# smog_v1_1_ctrl.net
KiCad netlist of a schematic drawn in EAGLE
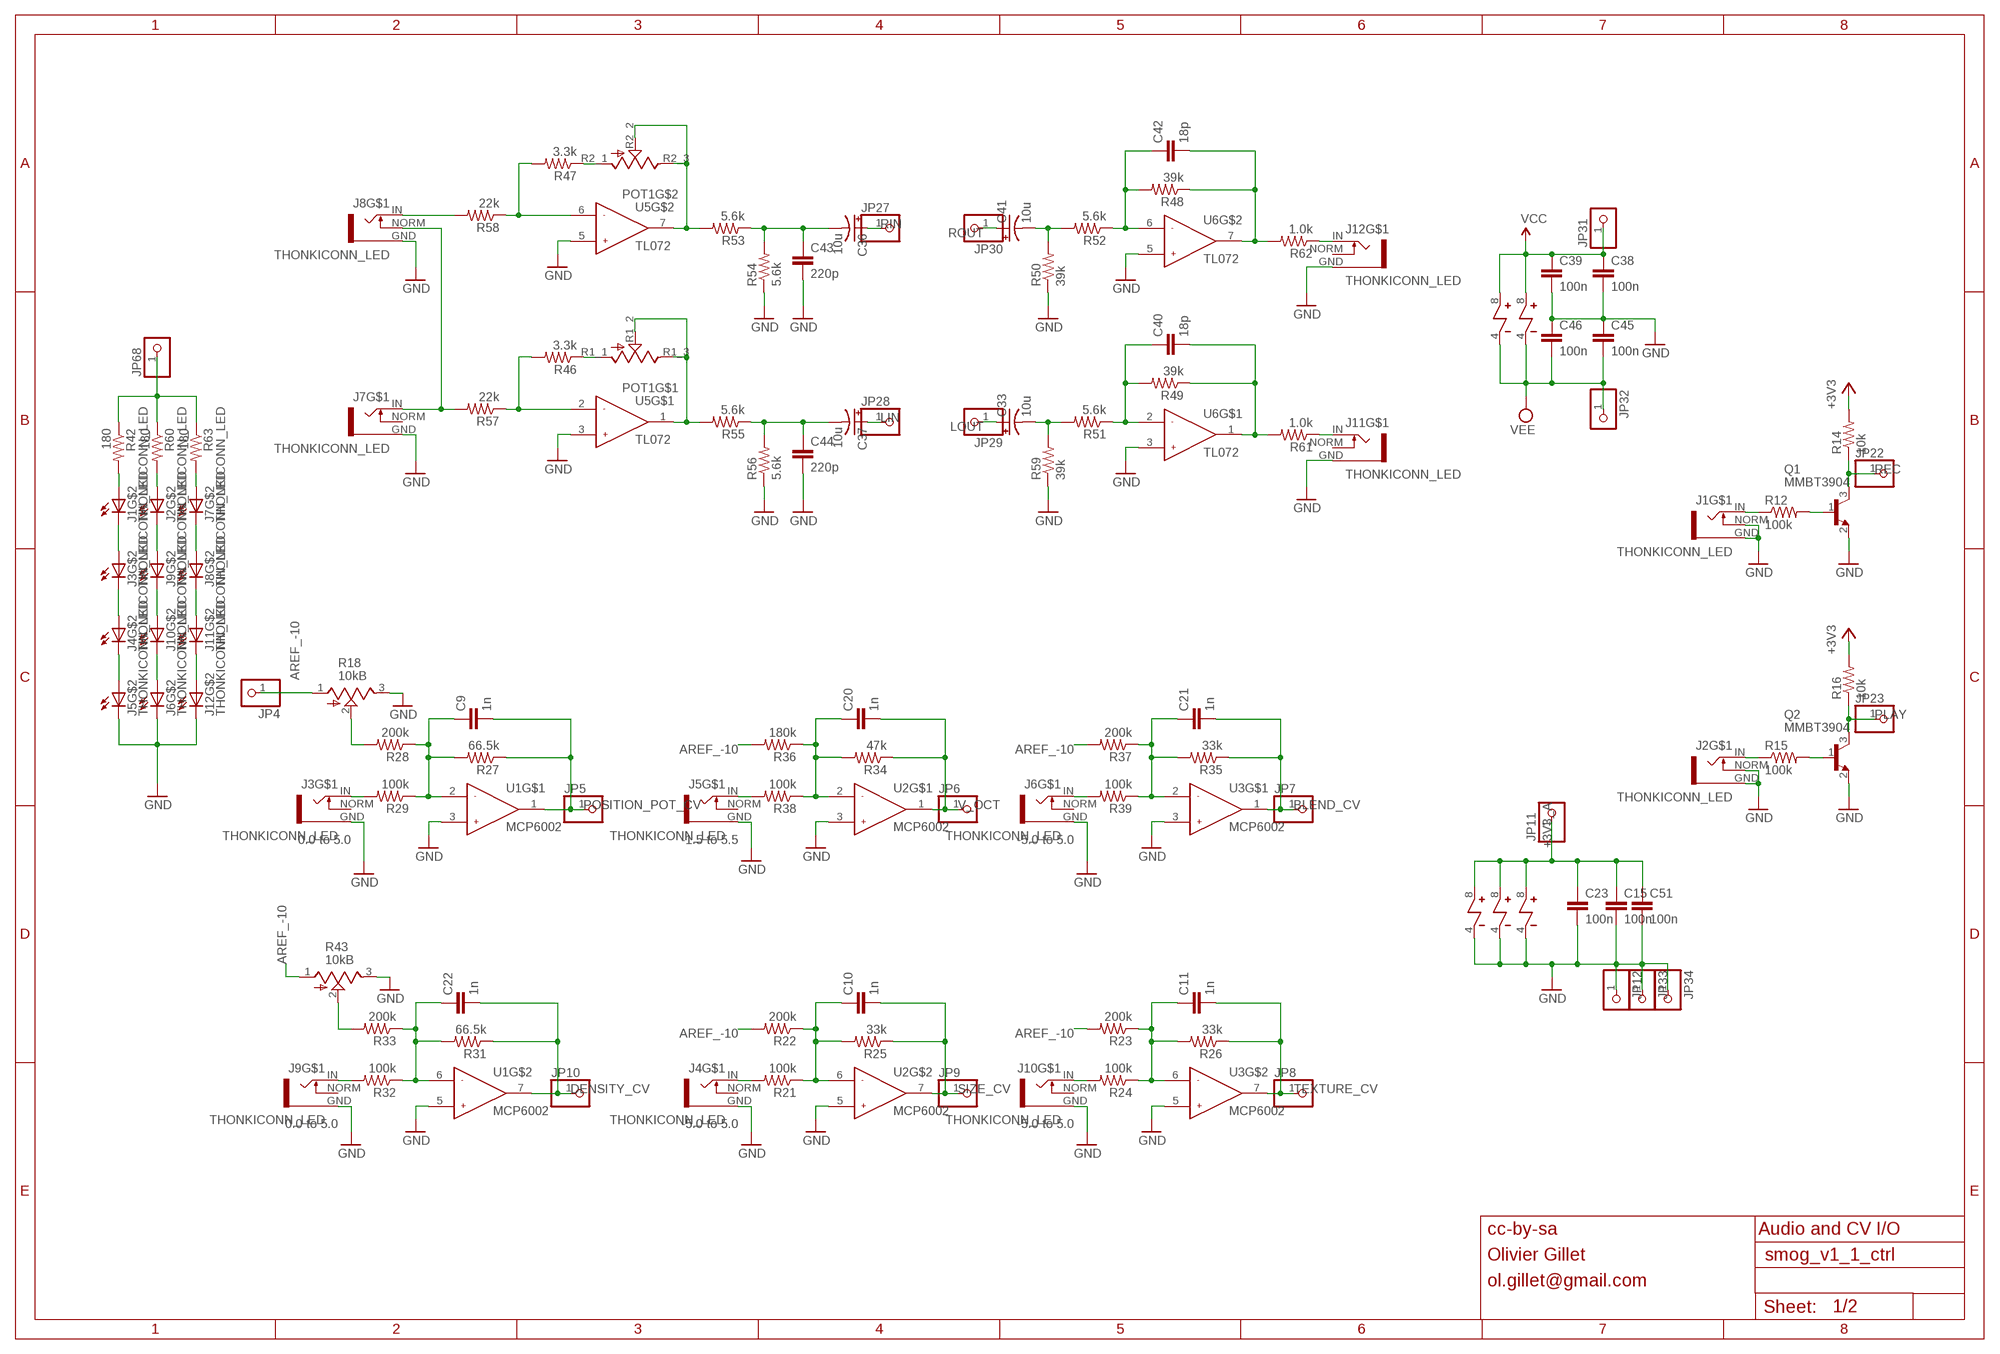
[diagram p0: schematic, sheet 1]
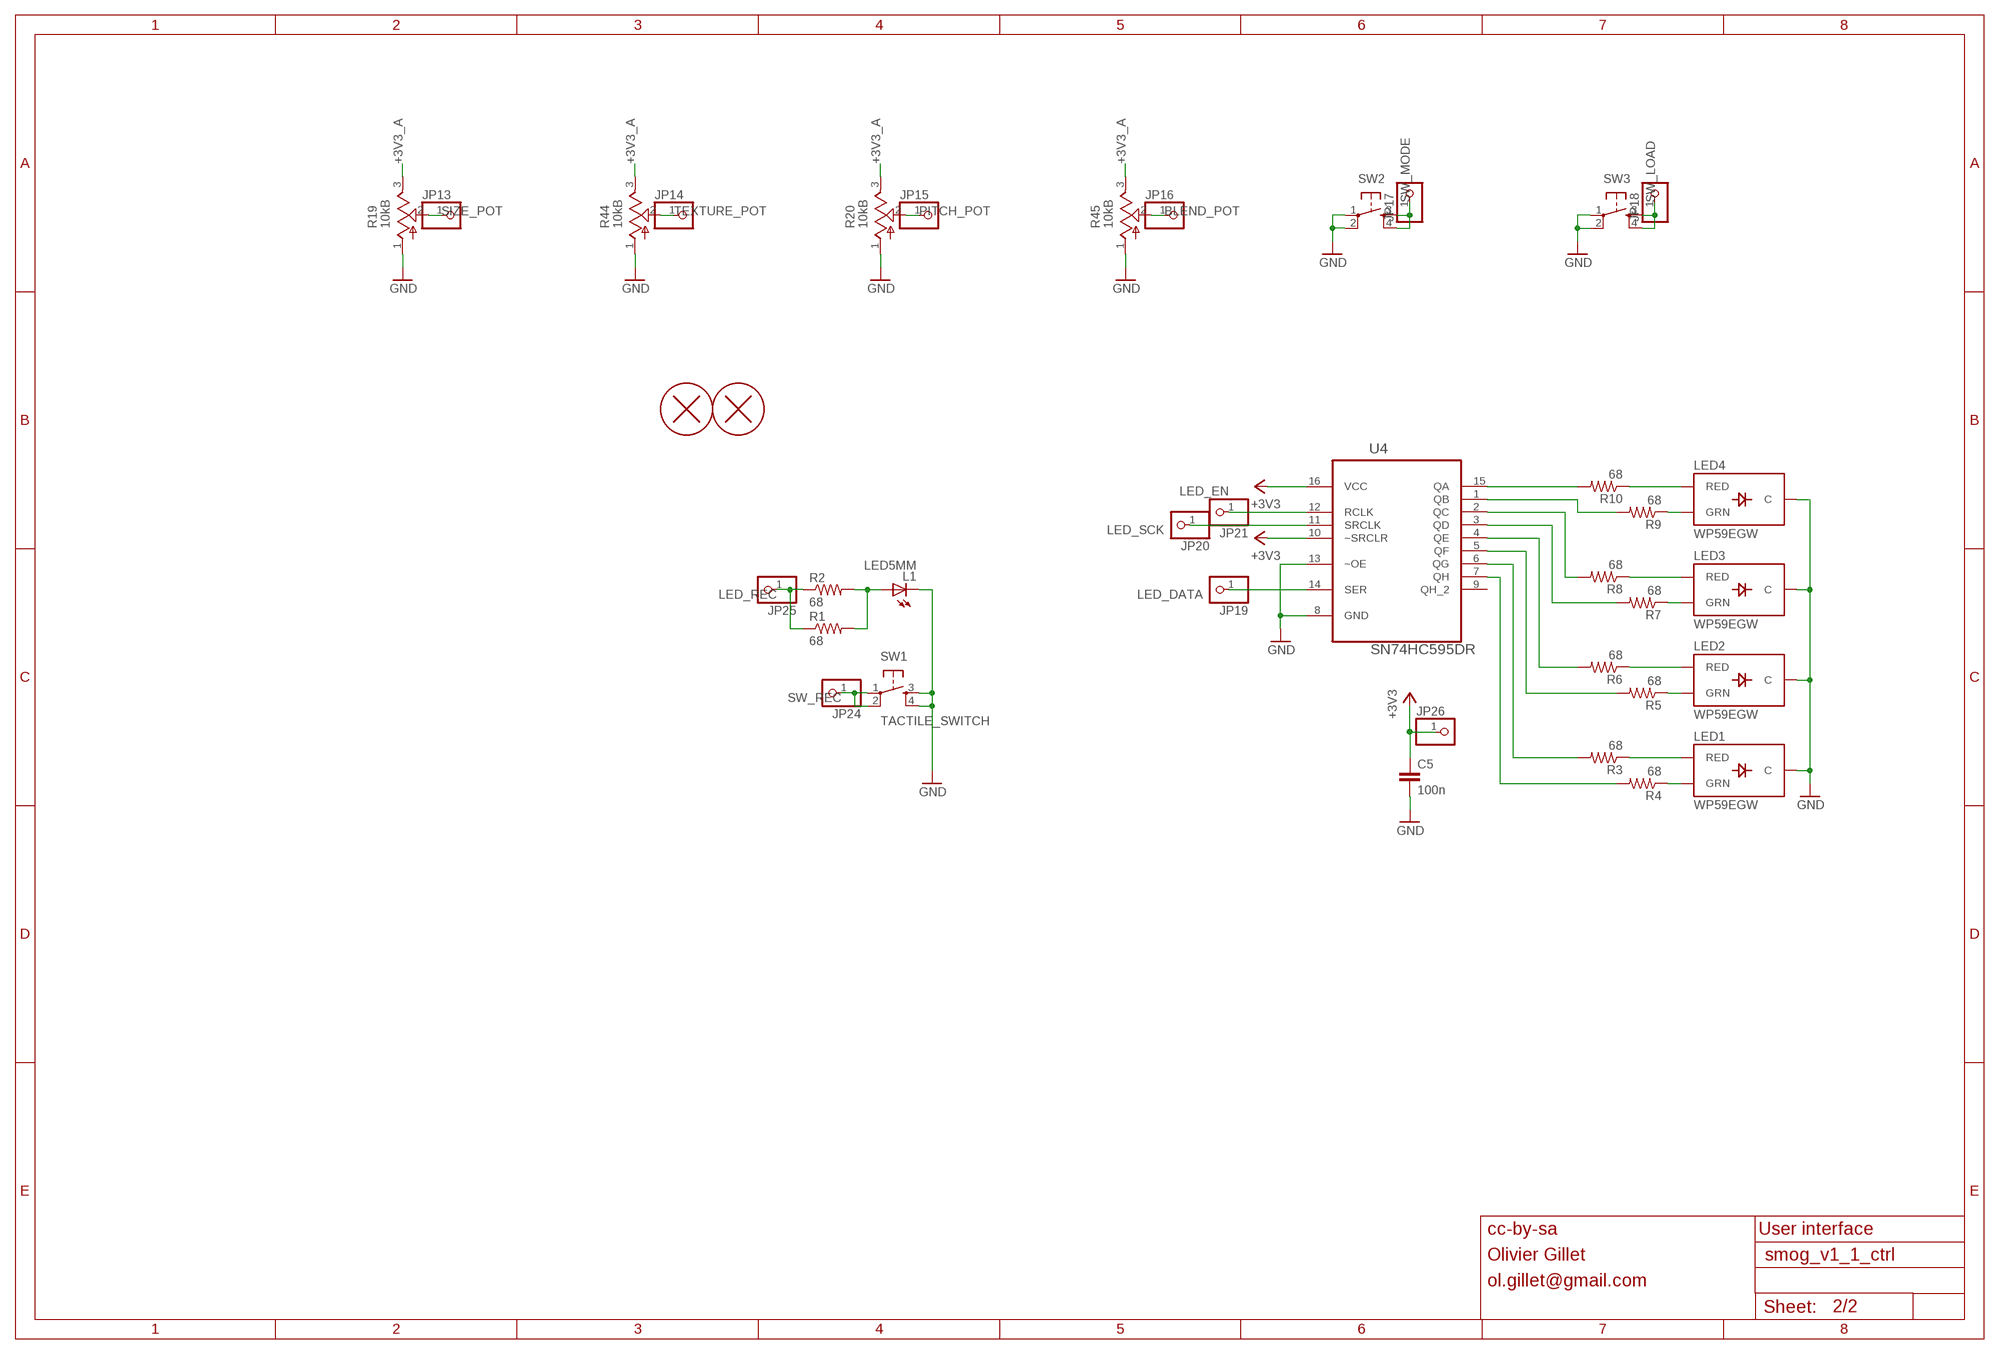
[diagram p1: schematic, sheet 2]

(export (version "E")
  (design (tool "Eeschema 10.0.6"))
  (components
    (comp (ref "C9")
      (value "1n")
      (footprint "eagle-import:RESISTOR_0603")
      (libsource (lib "eagle-import") (part "CAPACITOR"))
    )
    (comp (ref "C10")
      (value "1n")
      (footprint "eagle-import:RESISTOR_0603")
      (libsource (lib "eagle-import") (part "CAPACITOR"))
    )
    (comp (ref "C11")
      (value "1n")
      (footprint "eagle-import:RESISTOR_0603")
      (libsource (lib "eagle-import") (part "CAPACITOR"))
    )
    (comp (ref "C15")
      (value "100n")
      (footprint "eagle-import:RESISTOR_0603")
      (libsource (lib "eagle-import") (part "CAPACITOR"))
    )
    (comp (ref "C20")
      (value "1n")
      (footprint "eagle-import:RESISTOR_0603")
      (libsource (lib "eagle-import") (part "CAPACITOR"))
    )
    (comp (ref "C21")
      (value "1n")
      (footprint "eagle-import:RESISTOR_0603")
      (libsource (lib "eagle-import") (part "CAPACITOR"))
    )
    (comp (ref "C22")
      (value "1n")
      (footprint "eagle-import:RESISTOR_0603")
      (libsource (lib "eagle-import") (part "CAPACITOR"))
    )
    (comp (ref "C23")
      (value "100n")
      (footprint "eagle-import:RESISTOR_0603")
      (libsource (lib "eagle-import") (part "CAPACITOR"))
    )
    (comp (ref "C33")
      (value "10u")
      (footprint "eagle-import:PANASONIC_B")
      (libsource (lib "eagle-import") (part "CAP_POL"))
    )
    (comp (ref "C36")
      (value "10u")
      (footprint "eagle-import:PANASONIC_B")
      (libsource (lib "eagle-import") (part "CAP_POL"))
    )
    (comp (ref "C37")
      (value "10u")
      (footprint "eagle-import:PANASONIC_B")
      (libsource (lib "eagle-import") (part "CAP_POL"))
    )
    (comp (ref "C38")
      (value "100n")
      (footprint "eagle-import:RESISTOR_0603")
      (libsource (lib "eagle-import") (part "CAPACITOR"))
    )
    (comp (ref "C39")
      (value "100n")
      (footprint "eagle-import:RESISTOR_0603")
      (libsource (lib "eagle-import") (part "CAPACITOR"))
    )
    (comp (ref "C40")
      (value "18p")
      (footprint "eagle-import:RESISTOR_0603")
      (libsource (lib "eagle-import") (part "CAPACITOR"))
    )
    (comp (ref "C41")
      (value "10u")
      (footprint "eagle-import:PANASONIC_B")
      (libsource (lib "eagle-import") (part "CAP_POL"))
    )
    (comp (ref "C42")
      (value "18p")
      (footprint "eagle-import:RESISTOR_0603")
      (libsource (lib "eagle-import") (part "CAPACITOR"))
    )
    (comp (ref "C43")
      (value "220p")
      (footprint "eagle-import:RESISTOR_0603")
      (libsource (lib "eagle-import") (part "CAPACITOR"))
    )
    (comp (ref "C44")
      (value "220p")
      (footprint "eagle-import:RESISTOR_0603")
      (libsource (lib "eagle-import") (part "CAPACITOR"))
    )
    (comp (ref "C45")
      (value "100n")
      (footprint "eagle-import:RESISTOR_0603")
      (libsource (lib "eagle-import") (part "CAPACITOR"))
    )
    (comp (ref "C46")
      (value "100n")
      (footprint "eagle-import:RESISTOR_0603")
      (libsource (lib "eagle-import") (part "CAPACITOR"))
    )
    (comp (ref "C51")
      (value "100n")
      (footprint "eagle-import:RESISTOR_0603")
      (libsource (lib "eagle-import") (part "CAPACITOR"))
    )
    (comp (ref "J1")
      (value "THONKICONN_LED")
      (footprint "eagle-import:LED_JACK")
      (libsource (lib "eagle-import") (part "THONKICONN_LED"))
    )
    (comp (ref "J2")
      (value "THONKICONN_LED")
      (footprint "eagle-import:LED_JACK")
      (libsource (lib "eagle-import") (part "THONKICONN_LED"))
    )
    (comp (ref "J3")
      (value "THONKICONN_LED")
      (footprint "eagle-import:LED_JACK")
      (libsource (lib "eagle-import") (part "THONKICONN_LED"))
    )
    (comp (ref "J4")
      (value "THONKICONN_LED")
      (footprint "eagle-import:LED_JACK")
      (libsource (lib "eagle-import") (part "THONKICONN_LED"))
    )
    (comp (ref "J5")
      (value "THONKICONN_LED")
      (footprint "eagle-import:LED_JACK")
      (libsource (lib "eagle-import") (part "THONKICONN_LED"))
    )
    (comp (ref "J6")
      (value "THONKICONN_LED")
      (footprint "eagle-import:LED_JACK")
      (libsource (lib "eagle-import") (part "THONKICONN_LED"))
    )
    (comp (ref "J7")
      (value "THONKICONN_LED")
      (footprint "eagle-import:LED_JACK")
      (libsource (lib "eagle-import") (part "THONKICONN_LED"))
    )
    (comp (ref "J8")
      (value "THONKICONN_LED")
      (footprint "eagle-import:LED_JACK")
      (libsource (lib "eagle-import") (part "THONKICONN_LED"))
    )
    (comp (ref "J9")
      (value "THONKICONN_LED")
      (footprint "eagle-import:LED_JACK")
      (libsource (lib "eagle-import") (part "THONKICONN_LED"))
    )
    (comp (ref "J10")
      (value "THONKICONN_LED")
      (footprint "eagle-import:LED_JACK")
      (libsource (lib "eagle-import") (part "THONKICONN_LED"))
    )
    (comp (ref "J11")
      (value "THONKICONN_LED")
      (footprint "eagle-import:LED_JACK")
      (libsource (lib "eagle-import") (part "THONKICONN_LED"))
    )
    (comp (ref "J12")
      (value "THONKICONN_LED")
      (footprint "eagle-import:LED_JACK")
      (libsource (lib "eagle-import") (part "THONKICONN_LED"))
    )
    (comp (ref "JP4")
      (value "PINHD-1X1")
      (footprint "eagle-import:1X01")
      (libsource (lib "eagle-import") (part "PINHD-1X1"))
    )
    (comp (ref "JP5")
      (value "PINHD-1X1")
      (footprint "eagle-import:1X01")
      (libsource (lib "eagle-import") (part "PINHD-1X1"))
    )
    (comp (ref "JP6")
      (value "PINHD-1X1")
      (footprint "eagle-import:1X01")
      (libsource (lib "eagle-import") (part "PINHD-1X1"))
    )
    (comp (ref "JP7")
      (value "PINHD-1X1")
      (footprint "eagle-import:1X01")
      (libsource (lib "eagle-import") (part "PINHD-1X1"))
    )
    (comp (ref "JP8")
      (value "PINHD-1X1")
      (footprint "eagle-import:1X01")
      (libsource (lib "eagle-import") (part "PINHD-1X1"))
    )
    (comp (ref "JP9")
      (value "PINHD-1X1")
      (footprint "eagle-import:1X01")
      (libsource (lib "eagle-import") (part "PINHD-1X1"))
    )
    (comp (ref "JP10")
      (value "PINHD-1X1")
      (footprint "eagle-import:1X01")
      (libsource (lib "eagle-import") (part "PINHD-1X1"))
    )
    (comp (ref "JP11")
      (value "PINHD-1X1")
      (footprint "eagle-import:1X01")
      (libsource (lib "eagle-import") (part "PINHD-1X1"))
    )
    (comp (ref "JP12")
      (value "PINHD-1X1")
      (footprint "eagle-import:1X01")
      (libsource (lib "eagle-import") (part "PINHD-1X1"))
    )
    (comp (ref "JP22")
      (value "PINHD-1X1")
      (footprint "eagle-import:1X01")
      (libsource (lib "eagle-import") (part "PINHD-1X1"))
    )
    (comp (ref "JP23")
      (value "PINHD-1X1")
      (footprint "eagle-import:1X01")
      (libsource (lib "eagle-import") (part "PINHD-1X1"))
    )
    (comp (ref "JP27")
      (value "PINHD-1X1")
      (footprint "eagle-import:1X01")
      (libsource (lib "eagle-import") (part "PINHD-1X1"))
    )
    (comp (ref "JP28")
      (value "PINHD-1X1")
      (footprint "eagle-import:1X01")
      (libsource (lib "eagle-import") (part "PINHD-1X1"))
    )
    (comp (ref "JP29")
      (value "PINHD-1X1")
      (footprint "eagle-import:1X01")
      (libsource (lib "eagle-import") (part "PINHD-1X1"))
    )
    (comp (ref "JP30")
      (value "PINHD-1X1")
      (footprint "eagle-import:1X01")
      (libsource (lib "eagle-import") (part "PINHD-1X1"))
    )
    (comp (ref "JP31")
      (value "PINHD-1X1")
      (footprint "eagle-import:1X01")
      (libsource (lib "eagle-import") (part "PINHD-1X1"))
    )
    (comp (ref "JP32")
      (value "PINHD-1X1")
      (footprint "eagle-import:1X01")
      (libsource (lib "eagle-import") (part "PINHD-1X1"))
    )
    (comp (ref "JP33")
      (value "PINHD-1X1")
      (footprint "eagle-import:1X01")
      (libsource (lib "eagle-import") (part "PINHD-1X1"))
    )
    (comp (ref "JP34")
      (value "PINHD-1X1")
      (footprint "eagle-import:1X01")
      (libsource (lib "eagle-import") (part "PINHD-1X1"))
    )
    (comp (ref "JP68")
      (value "PINHD-1X1")
      (footprint "eagle-import:1X01")
      (libsource (lib "eagle-import") (part "PINHD-1X1"))
    )
    (comp (ref "POT1")
      (value "POT_DUAL_THONK")
      (footprint "eagle-import:POT_DUAL_THONK")
      (libsource (lib "eagle-import") (part "POT_DUAL_THONK"))
    )
    (comp (ref "Q1")
      (value "MMBT3904")
      (footprint "eagle-import:SOT23")
      (libsource (lib "eagle-import") (part "MMBT3904SOT23"))
    )
    (comp (ref "Q2")
      (value "MMBT3904")
      (footprint "eagle-import:SOT23")
      (libsource (lib "eagle-import") (part "MMBT3904SOT23"))
    )
    (comp (ref "R12")
      (value "100k")
      (footprint "eagle-import:RESISTOR_0603")
      (libsource (lib "eagle-import") (part "RESISTOR"))
    )
    (comp (ref "R14")
      (value "10k")
      (footprint "eagle-import:RESISTOR_0603")
      (libsource (lib "eagle-import") (part "RESISTOR"))
    )
    (comp (ref "R15")
      (value "100k")
      (footprint "eagle-import:RESISTOR_0603")
      (libsource (lib "eagle-import") (part "RESISTOR"))
    )
    (comp (ref "R16")
      (value "10k")
      (footprint "eagle-import:RESISTOR_0603")
      (libsource (lib "eagle-import") (part "RESISTOR"))
    )
    (comp (ref "R18")
      (value "10kB")
      (footprint "eagle-import:ALPS_POT_VERTICAL")
      (libsource (lib "eagle-import") (part "POT_VERTICAL"))
    )
    (comp (ref "R21")
      (value "100k")
      (footprint "eagle-import:RESISTOR_0603")
      (libsource (lib "eagle-import") (part "RESISTOR"))
    )
    (comp (ref "R22")
      (value "200k")
      (footprint "eagle-import:RESISTOR_0603")
      (libsource (lib "eagle-import") (part "RESISTOR"))
    )
    (comp (ref "R23")
      (value "200k")
      (footprint "eagle-import:RESISTOR_0603")
      (libsource (lib "eagle-import") (part "RESISTOR"))
    )
    (comp (ref "R24")
      (value "100k")
      (footprint "eagle-import:RESISTOR_0603")
      (libsource (lib "eagle-import") (part "RESISTOR"))
    )
    (comp (ref "R25")
      (value "33k")
      (footprint "eagle-import:RESISTOR_0603")
      (libsource (lib "eagle-import") (part "RESISTOR"))
    )
    (comp (ref "R26")
      (value "33k")
      (footprint "eagle-import:RESISTOR_0603")
      (libsource (lib "eagle-import") (part "RESISTOR"))
    )
    (comp (ref "R27")
      (value "66.5k")
      (footprint "eagle-import:RESISTOR_0603")
      (libsource (lib "eagle-import") (part "RESISTOR"))
    )
    (comp (ref "R28")
      (value "200k")
      (footprint "eagle-import:RESISTOR_0603")
      (libsource (lib "eagle-import") (part "RESISTOR"))
    )
    (comp (ref "R29")
      (value "100k")
      (footprint "eagle-import:RESISTOR_0603")
      (libsource (lib "eagle-import") (part "RESISTOR"))
    )
    (comp (ref "R31")
      (value "66.5k")
      (footprint "eagle-import:RESISTOR_0603")
      (libsource (lib "eagle-import") (part "RESISTOR"))
    )
    (comp (ref "R32")
      (value "100k")
      (footprint "eagle-import:RESISTOR_0603")
      (libsource (lib "eagle-import") (part "RESISTOR"))
    )
    (comp (ref "R33")
      (value "200k")
      (footprint "eagle-import:RESISTOR_0603")
      (libsource (lib "eagle-import") (part "RESISTOR"))
    )
    (comp (ref "R34")
      (value "47k")
      (footprint "eagle-import:RESISTOR_0603")
      (libsource (lib "eagle-import") (part "RESISTOR"))
    )
    (comp (ref "R35")
      (value "33k")
      (footprint "eagle-import:RESISTOR_0603")
      (libsource (lib "eagle-import") (part "RESISTOR"))
    )
    (comp (ref "R36")
      (value "180k")
      (footprint "eagle-import:RESISTOR_0603")
      (libsource (lib "eagle-import") (part "RESISTOR"))
    )
    (comp (ref "R37")
      (value "200k")
      (footprint "eagle-import:RESISTOR_0603")
      (libsource (lib "eagle-import") (part "RESISTOR"))
    )
    (comp (ref "R38")
      (value "100k")
      (footprint "eagle-import:RESISTOR_0603")
      (libsource (lib "eagle-import") (part "RESISTOR"))
    )
    (comp (ref "R39")
      (value "100k")
      (footprint "eagle-import:RESISTOR_0603")
      (libsource (lib "eagle-import") (part "RESISTOR"))
    )
    (comp (ref "R42")
      (value "180")
      (footprint "eagle-import:RESISTOR_0603")
      (libsource (lib "eagle-import") (part "RESISTOR"))
    )
    (comp (ref "R43")
      (value "10kB")
      (footprint "eagle-import:ALPS_POT_VERTICAL")
      (libsource (lib "eagle-import") (part "POT_VERTICAL"))
    )
    (comp (ref "R46")
      (value "3.3k")
      (footprint "eagle-import:RESISTOR_0603")
      (libsource (lib "eagle-import") (part "RESISTOR"))
    )
    (comp (ref "R47")
      (value "3.3k")
      (footprint "eagle-import:RESISTOR_0603")
      (libsource (lib "eagle-import") (part "RESISTOR"))
    )
    (comp (ref "R48")
      (value "39k")
      (footprint "eagle-import:RESISTOR_0603")
      (libsource (lib "eagle-import") (part "RESISTOR"))
    )
    (comp (ref "R49")
      (value "39k")
      (footprint "eagle-import:RESISTOR_0603")
      (libsource (lib "eagle-import") (part "RESISTOR"))
    )
    (comp (ref "R50")
      (value "39k")
      (footprint "eagle-import:RESISTOR_0603")
      (libsource (lib "eagle-import") (part "RESISTOR"))
    )
    (comp (ref "R51")
      (value "5.6k")
      (footprint "eagle-import:RESISTOR_0603")
      (libsource (lib "eagle-import") (part "RESISTOR"))
    )
    (comp (ref "R52")
      (value "5.6k")
      (footprint "eagle-import:RESISTOR_0603")
      (libsource (lib "eagle-import") (part "RESISTOR"))
    )
    (comp (ref "R53")
      (value "5.6k")
      (footprint "eagle-import:RESISTOR_0603")
      (libsource (lib "eagle-import") (part "RESISTOR"))
    )
    (comp (ref "R54")
      (value "5.6k")
      (footprint "eagle-import:RESISTOR_0603")
      (libsource (lib "eagle-import") (part "RESISTOR"))
    )
    (comp (ref "R55")
      (value "5.6k")
      (footprint "eagle-import:RESISTOR_0603")
      (libsource (lib "eagle-import") (part "RESISTOR"))
    )
    (comp (ref "R56")
      (value "5.6k")
      (footprint "eagle-import:RESISTOR_0603")
      (libsource (lib "eagle-import") (part "RESISTOR"))
    )
    (comp (ref "R57")
      (value "22k")
      (footprint "eagle-import:RESISTOR_0603")
      (libsource (lib "eagle-import") (part "RESISTOR"))
    )
    (comp (ref "R58")
      (value "22k")
      (footprint "eagle-import:RESISTOR_0603")
      (libsource (lib "eagle-import") (part "RESISTOR"))
    )
    (comp (ref "R59")
      (value "39k")
      (footprint "eagle-import:RESISTOR_0603")
      (libsource (lib "eagle-import") (part "RESISTOR"))
    )
    (comp (ref "R60")
      (value "180")
      (footprint "eagle-import:RESISTOR_0603")
      (libsource (lib "eagle-import") (part "RESISTOR"))
    )
    (comp (ref "R61")
      (value "1.0k")
      (footprint "eagle-import:RESISTOR_0603")
      (libsource (lib "eagle-import") (part "RESISTOR"))
    )
    (comp (ref "R62")
      (value "1.0k")
      (footprint "eagle-import:RESISTOR_0603")
      (libsource (lib "eagle-import") (part "RESISTOR"))
    )
    (comp (ref "R63")
      (value "180")
      (footprint "eagle-import:RESISTOR_0603")
      (libsource (lib "eagle-import") (part "RESISTOR"))
    )
    (comp (ref "U1")
      (value "MCP6002")
      (footprint "eagle-import:SOIC8")
      (libsource (lib "eagle-import") (part "OPAMP_DUAL"))
    )
    (comp (ref "U2")
      (value "MCP6002")
      (footprint "eagle-import:SOIC8")
      (libsource (lib "eagle-import") (part "OPAMP_DUAL"))
    )
    (comp (ref "U3")
      (value "MCP6002")
      (footprint "eagle-import:SOIC8")
      (libsource (lib "eagle-import") (part "OPAMP_DUAL"))
    )
    (comp (ref "U5")
      (value "TL072")
      (footprint "eagle-import:SOIC8")
      (libsource (lib "eagle-import") (part "OPAMP_DUAL"))
    )
    (comp (ref "U6")
      (value "TL072")
      (footprint "eagle-import:SOIC8")
      (libsource (lib "eagle-import") (part "OPAMP_DUAL"))
    )
    (comp (ref "C5")
      (value "100n")
      (footprint "eagle-import:RESISTOR_0603")
      (libsource (lib "eagle-import") (part "CAPACITOR"))
    )
    (comp (ref "H1")
      (value "PCB_SCREW")
      (footprint "eagle-import:PCB_SCREW")
      (libsource (lib "eagle-import") (part "PCB_SCREW"))
    )
    (comp (ref "H2")
      (value "PCB_SCREW")
      (footprint "eagle-import:PCB_SCREW")
      (libsource (lib "eagle-import") (part "PCB_SCREW"))
    )
    (comp (ref "JP13")
      (value "PINHD-1X1")
      (footprint "eagle-import:1X01")
      (libsource (lib "eagle-import") (part "PINHD-1X1"))
    )
    (comp (ref "JP14")
      (value "PINHD-1X1")
      (footprint "eagle-import:1X01")
      (libsource (lib "eagle-import") (part "PINHD-1X1"))
    )
    (comp (ref "JP15")
      (value "PINHD-1X1")
      (footprint "eagle-import:1X01")
      (libsource (lib "eagle-import") (part "PINHD-1X1"))
    )
    (comp (ref "JP16")
      (value "PINHD-1X1")
      (footprint "eagle-import:1X01")
      (libsource (lib "eagle-import") (part "PINHD-1X1"))
    )
    (comp (ref "JP17")
      (value "PINHD-1X1")
      (footprint "eagle-import:1X01")
      (libsource (lib "eagle-import") (part "PINHD-1X1"))
    )
    (comp (ref "JP18")
      (value "PINHD-1X1")
      (footprint "eagle-import:1X01")
      (libsource (lib "eagle-import") (part "PINHD-1X1"))
    )
    (comp (ref "JP19")
      (value "PINHD-1X1")
      (footprint "eagle-import:1X01")
      (libsource (lib "eagle-import") (part "PINHD-1X1"))
    )
    (comp (ref "JP20")
      (value "PINHD-1X1")
      (footprint "eagle-import:1X01")
      (libsource (lib "eagle-import") (part "PINHD-1X1"))
    )
    (comp (ref "JP21")
      (value "PINHD-1X1")
      (footprint "eagle-import:1X01")
      (libsource (lib "eagle-import") (part "PINHD-1X1"))
    )
    (comp (ref "JP24")
      (value "PINHD-1X1")
      (footprint "eagle-import:1X01")
      (libsource (lib "eagle-import") (part "PINHD-1X1"))
    )
    (comp (ref "JP25")
      (value "PINHD-1X1")
      (footprint "eagle-import:1X01")
      (libsource (lib "eagle-import") (part "PINHD-1X1"))
    )
    (comp (ref "JP26")
      (value "PINHD-1X1")
      (footprint "eagle-import:1X01")
      (libsource (lib "eagle-import") (part "PINHD-1X1"))
    )
    (comp (ref "L1")
      (value "LED5MM")
      (footprint "eagle-import:LED_5MM")
      (libsource (lib "eagle-import") (part "LED5MM"))
    )
    (comp (ref "LED1")
      (value "WP59EGW")
      (footprint "eagle-import:LED_BICOLOR")
      (libsource (lib "eagle-import") (part "LED_BICOLOR_THROUGHHOLE"))
    )
    (comp (ref "LED2")
      (value "WP59EGW")
      (footprint "eagle-import:LED_BICOLOR")
      (libsource (lib "eagle-import") (part "LED_BICOLOR_THROUGHHOLE"))
    )
    (comp (ref "LED3")
      (value "WP59EGW")
      (footprint "eagle-import:LED_BICOLOR")
      (libsource (lib "eagle-import") (part "LED_BICOLOR_THROUGHHOLE"))
    )
    (comp (ref "LED4")
      (value "WP59EGW")
      (footprint "eagle-import:LED_BICOLOR")
      (libsource (lib "eagle-import") (part "LED_BICOLOR_THROUGHHOLE"))
    )
    (comp (ref "R1")
      (value "68")
      (footprint "eagle-import:RESISTOR_0603")
      (libsource (lib "eagle-import") (part "RESISTOR"))
    )
    (comp (ref "R2")
      (value "68")
      (footprint "eagle-import:RESISTOR_0603")
      (libsource (lib "eagle-import") (part "RESISTOR"))
    )
    (comp (ref "R3")
      (value "68")
      (footprint "eagle-import:RESISTOR_0603")
      (libsource (lib "eagle-import") (part "RESISTOR"))
    )
    (comp (ref "R4")
      (value "68")
      (footprint "eagle-import:RESISTOR_0603")
      (libsource (lib "eagle-import") (part "RESISTOR"))
    )
    (comp (ref "R5")
      (value "68")
      (footprint "eagle-import:RESISTOR_0603")
      (libsource (lib "eagle-import") (part "RESISTOR"))
    )
    (comp (ref "R6")
      (value "68")
      (footprint "eagle-import:RESISTOR_0603")
      (libsource (lib "eagle-import") (part "RESISTOR"))
    )
    (comp (ref "R7")
      (value "68")
      (footprint "eagle-import:RESISTOR_0603")
      (libsource (lib "eagle-import") (part "RESISTOR"))
    )
    (comp (ref "R8")
      (value "68")
      (footprint "eagle-import:RESISTOR_0603")
      (libsource (lib "eagle-import") (part "RESISTOR"))
    )
    (comp (ref "R9")
      (value "68")
      (footprint "eagle-import:RESISTOR_0603")
      (libsource (lib "eagle-import") (part "RESISTOR"))
    )
    (comp (ref "R10")
      (value "68")
      (footprint "eagle-import:RESISTOR_0603")
      (libsource (lib "eagle-import") (part "RESISTOR"))
    )
    (comp (ref "R19")
      (value "10kB")
      (footprint "eagle-import:ALPS_POT_VERTICAL")
      (libsource (lib "eagle-import") (part "POT_VERTICAL"))
    )
    (comp (ref "R20")
      (value "10kB")
      (footprint "eagle-import:ALPS_POT_VERTICAL")
      (libsource (lib "eagle-import") (part "POT_VERTICAL"))
    )
    (comp (ref "R44")
      (value "10kB")
      (footprint "eagle-import:ALPS_POT_VERTICAL")
      (libsource (lib "eagle-import") (part "POT_VERTICAL"))
    )
    (comp (ref "R45")
      (value "10kB")
      (footprint "eagle-import:ALPS_POT_VERTICAL")
      (libsource (lib "eagle-import") (part "POT_VERTICAL"))
    )
    (comp (ref "SW1")
      (value "TACTILE_SWITCH")
      (footprint "eagle-import:TACTILE-PTH")
      (libsource (lib "eagle-import") (part "TACTILE_SWITCH"))
    )
    (comp (ref "SW2")
      (value "TACTILE_SWITCH")
      (footprint "eagle-import:TACTILE-PTH")
      (libsource (lib "eagle-import") (part "TACTILE_SWITCH"))
    )
    (comp (ref "SW3")
      (value "TACTILE_SWITCH")
      (footprint "eagle-import:TACTILE-PTH")
      (libsource (lib "eagle-import") (part "TACTILE_SWITCH"))
    )
    (comp (ref "U4")
      (value "SN74HC595DR")
      (footprint "eagle-import:SOIC16")
      (libsource (lib "eagle-import") (part "SN74HC595DR"))
    )
  )
  (nets
    (net (code "1") (name "+3V3") (class "Default")
      (node (ref "C5") (pin "1") (pinfunction "1_1") (pintype "passive"))
      (node (ref "JP26") (pin "1") (pinfunction "1_1") (pintype "passive"))
      (node (ref "R14") (pin "2") (pinfunction "2_2") (pintype "passive"))
      (node (ref "R16") (pin "2") (pinfunction "2_2") (pintype "passive"))
      (node (ref "U4") (pin "10") (pinfunction "~{SRCLR}_10") (pintype "input"))
      (node (ref "U4") (pin "16") (pinfunction "VCC_16") (pintype "power_in"))
    )
    (net (code "2") (name "+3V3_A") (class "Default")
      (node (ref "C15") (pin "1") (pinfunction "1_1") (pintype "passive"))
      (node (ref "C23") (pin "1") (pinfunction "1_1") (pintype "passive"))
      (node (ref "C51") (pin "1") (pinfunction "1_1") (pintype "passive"))
      (node (ref "JP11") (pin "1") (pinfunction "1_1") (pintype "passive"))
      (node (ref "R19") (pin "3") (pinfunction "B_3") (pintype "passive"))
      (node (ref "R20") (pin "3") (pinfunction "B_3") (pintype "passive"))
      (node (ref "R44") (pin "3") (pinfunction "B_3") (pintype "passive"))
      (node (ref "R45") (pin "3") (pinfunction "B_3") (pintype "passive"))
      (node (ref "U1") (pin "8") (pinfunction "P$1_8") (pintype "bidirectional"))
      (node (ref "U2") (pin "8") (pinfunction "P$1_8") (pintype "bidirectional"))
      (node (ref "U3") (pin "8") (pinfunction "P$1_8") (pintype "bidirectional"))
    )
    (net (code "3") (name "AREF_-10") (class "Default")
      (node (ref "JP4") (pin "1") (pinfunction "1_1") (pintype "passive"))
      (node (ref "R18") (pin "1") (pinfunction "A_1") (pintype "passive"))
      (node (ref "R22") (pin "2") (pinfunction "2_2") (pintype "passive"))
      (node (ref "R23") (pin "2") (pinfunction "2_2") (pintype "passive"))
      (node (ref "R36") (pin "2") (pinfunction "2_2") (pintype "passive"))
      (node (ref "R37") (pin "2") (pinfunction "2_2") (pintype "passive"))
      (node (ref "R43") (pin "1") (pinfunction "A_1") (pintype "passive"))
    )
    (net (code "4") (name "BLEND_CV") (class "Default")
      (node (ref "C21") (pin "2") (pinfunction "2_2") (pintype "passive"))
      (node (ref "JP7") (pin "1") (pinfunction "1_1") (pintype "passive"))
      (node (ref "R35") (pin "1") (pinfunction "1_1") (pintype "passive"))
      (node (ref "U3") (pin "1") (pinfunction "P$3_1") (pintype "bidirectional"))
    )
    (net (code "5") (name "BLEND_POT") (class "Default")
      (node (ref "JP16") (pin "1") (pinfunction "1_1") (pintype "passive"))
      (node (ref "R45") (pin "2") (pinfunction "W_2") (pintype "passive"))
    )
    (net (code "6") (name "DENSITY_CV") (class "Default")
      (node (ref "C22") (pin "2") (pinfunction "2_2") (pintype "passive"))
      (node (ref "JP10") (pin "1") (pinfunction "1_1") (pintype "passive"))
      (node (ref "R31") (pin "1") (pinfunction "1_1") (pintype "passive"))
      (node (ref "U1") (pin "7") (pinfunction "P$3_7") (pintype "bidirectional"))
    )
    (net (code "7") (name "GND") (class "Default")
      (node (ref "C15") (pin "2") (pinfunction "2_2") (pintype "passive"))
      (node (ref "C23") (pin "2") (pinfunction "2_2") (pintype "passive"))
      (node (ref "C38") (pin "2") (pinfunction "2_2") (pintype "passive"))
      (node (ref "C39") (pin "2") (pinfunction "2_2") (pintype "passive"))
      (node (ref "C43") (pin "2") (pinfunction "2_2") (pintype "passive"))
      (node (ref "C44") (pin "2") (pinfunction "2_2") (pintype "passive"))
      (node (ref "C45") (pin "1") (pinfunction "1_1") (pintype "passive"))
      (node (ref "C46") (pin "1") (pinfunction "1_1") (pintype "passive"))
      (node (ref "C5") (pin "2") (pinfunction "2_2") (pintype "passive"))
      (node (ref "C51") (pin "2") (pinfunction "2_2") (pintype "passive"))
      (node (ref "J1") (pin "GND") (pinfunction "GND_GND") (pintype "passive"))
      (node (ref "J1") (pin "NORM") (pinfunction "NORM_NORM") (pintype "passive"))
      (node (ref "J10") (pin "GND") (pinfunction "GND_GND") (pintype "passive"))
      (node (ref "J11") (pin "GND") (pinfunction "GND_GND") (pintype "passive"))
      (node (ref "J12") (pin "C") (pinfunction "C_C") (pintype "passive"))
      (node (ref "J12") (pin "GND") (pinfunction "GND_GND") (pintype "passive"))
      (node (ref "J2") (pin "GND") (pinfunction "GND_GND") (pintype "passive"))
      (node (ref "J2") (pin "NORM") (pinfunction "NORM_NORM") (pintype "passive"))
      (node (ref "J3") (pin "GND") (pinfunction "GND_GND") (pintype "passive"))
      (node (ref "J4") (pin "GND") (pinfunction "GND_GND") (pintype "passive"))
      (node (ref "J5") (pin "C") (pinfunction "C_C") (pintype "passive"))
      (node (ref "J5") (pin "GND") (pinfunction "GND_GND") (pintype "passive"))
      (node (ref "J6") (pin "C") (pinfunction "C_C") (pintype "passive"))
      (node (ref "J6") (pin "GND") (pinfunction "GND_GND") (pintype "passive"))
      (node (ref "J7") (pin "GND") (pinfunction "GND_GND") (pintype "passive"))
      (node (ref "J8") (pin "GND") (pinfunction "GND_GND") (pintype "passive"))
      (node (ref "J9") (pin "GND") (pinfunction "GND_GND") (pintype "passive"))
      (node (ref "JP12") (pin "1") (pinfunction "1_1") (pintype "passive"))
      (node (ref "JP33") (pin "1") (pinfunction "1_1") (pintype "passive"))
      (node (ref "JP34") (pin "1") (pinfunction "1_1") (pintype "passive"))
      (node (ref "L1") (pin "K") (pinfunction "C_K") (pintype "passive"))
      (node (ref "LED1") (pin "2") (pinfunction "C_2") (pintype "bidirectional"))
      (node (ref "LED2") (pin "2") (pinfunction "C_2") (pintype "bidirectional"))
      (node (ref "LED3") (pin "2") (pinfunction "C_2") (pintype "bidirectional"))
      (node (ref "LED4") (pin "2") (pinfunction "C_2") (pintype "bidirectional"))
      (node (ref "Q1") (pin "2") (pinfunction "E_2") (pintype "passive"))
      (node (ref "Q2") (pin "2") (pinfunction "E_2") (pintype "passive"))
      (node (ref "R18") (pin "3") (pinfunction "B_3") (pintype "passive"))
      (node (ref "R19") (pin "1") (pinfunction "A_1") (pintype "passive"))
      (node (ref "R20") (pin "1") (pinfunction "A_1") (pintype "passive"))
      (node (ref "R43") (pin "3") (pinfunction "B_3") (pintype "passive"))
      (node (ref "R44") (pin "1") (pinfunction "A_1") (pintype "passive"))
      (node (ref "R45") (pin "1") (pinfunction "A_1") (pintype "passive"))
      (node (ref "R50") (pin "1") (pinfunction "1_1") (pintype "passive"))
      (node (ref "R54") (pin "1") (pinfunction "1_1") (pintype "passive"))
      (node (ref "R56") (pin "1") (pinfunction "1_1") (pintype "passive"))
      (node (ref "R59") (pin "1") (pinfunction "1_1") (pintype "passive"))
      (node (ref "SW1") (pin "3") (pinfunction "3_3") (pintype "passive"))
      (node (ref "SW1") (pin "4") (pinfunction "4_4") (pintype "passive"))
      (node (ref "SW2") (pin "1") (pinfunction "1_1") (pintype "passive"))
      (node (ref "SW2") (pin "2") (pinfunction "2_2") (pintype "passive"))
      (node (ref "SW3") (pin "1") (pinfunction "1_1") (pintype "passive"))
      (node (ref "SW3") (pin "2") (pinfunction "2_2") (pintype "passive"))
      (node (ref "U1") (pin "3") (pinfunction "P$1_3") (pintype "bidirectional"))
      (node (ref "U1") (pin "4") (pinfunction "P$2_4") (pintype "bidirectional"))
      (node (ref "U1") (pin "5") (pinfunction "P$1_5") (pintype "bidirectional"))
      (node (ref "U2") (pin "3") (pinfunction "P$1_3") (pintype "bidirectional"))
      (node (ref "U2") (pin "4") (pinfunction "P$2_4") (pintype "bidirectional"))
      (node (ref "U2") (pin "5") (pinfunction "P$1_5") (pintype "bidirectional"))
      (node (ref "U3") (pin "3") (pinfunction "P$1_3") (pintype "bidirectional"))
      (node (ref "U3") (pin "4") (pinfunction "P$2_4") (pintype "bidirectional"))
      (node (ref "U3") (pin "5") (pinfunction "P$1_5") (pintype "bidirectional"))
      (node (ref "U4") (pin "13") (pinfunction "~{OE}_13") (pintype "input"))
      (node (ref "U4") (pin "8") (pinfunction "GND_8") (pintype "passive"))
      (node (ref "U5") (pin "3") (pinfunction "P$1_3") (pintype "bidirectional"))
      (node (ref "U5") (pin "5") (pinfunction "P$1_5") (pintype "bidirectional"))
      (node (ref "U6") (pin "3") (pinfunction "P$1_3") (pintype "bidirectional"))
      (node (ref "U6") (pin "5") (pinfunction "P$1_5") (pintype "bidirectional"))
    )
    (net (code "8") (name "LED_DATA") (class "Default")
      (node (ref "JP19") (pin "1") (pinfunction "1_1") (pintype "passive"))
      (node (ref "U4") (pin "14") (pinfunction "SER_14") (pintype "input"))
    )
    (net (code "9") (name "LED_EN") (class "Default")
      (node (ref "JP21") (pin "1") (pinfunction "1_1") (pintype "passive"))
      (node (ref "U4") (pin "12") (pinfunction "RCLK_12") (pintype "input"))
    )
    (net (code "10") (name "LED_REC") (class "Default")
      (node (ref "JP25") (pin "1") (pinfunction "1_1") (pintype "passive"))
      (node (ref "R1") (pin "1") (pinfunction "1_1") (pintype "passive"))
      (node (ref "R2") (pin "1") (pinfunction "1_1") (pintype "passive"))
    )
    (net (code "11") (name "LED_SCK") (class "Default")
      (node (ref "JP20") (pin "1") (pinfunction "1_1") (pintype "passive"))
      (node (ref "U4") (pin "11") (pinfunction "SRCLK_11") (pintype "input"))
    )
    (net (code "12") (name "LIN") (class "Default")
      (node (ref "C37") (pin "+") (pinfunction "+_+") (pintype "passive"))
      (node (ref "JP28") (pin "1") (pinfunction "1_1") (pintype "passive"))
    )
    (net (code "13") (name "LOUT") (class "Default")
      (node (ref "C33") (pin "+") (pinfunction "+_+") (pintype "passive"))
      (node (ref "JP29") (pin "1") (pinfunction "1_1") (pintype "passive"))
    )
    (net (code "14") (name "Net-(C33-Pad-)") (class "Default")
      (node (ref "C33") (pin "-") (pinfunction "-_-") (pintype "passive"))
      (node (ref "R51") (pin "2") (pinfunction "2_2") (pintype "passive"))
      (node (ref "R59") (pin "2") (pinfunction "2_2") (pintype "passive"))
    )
    (net (code "15") (name "Net-(C36-Pad-)") (class "Default")
      (node (ref "C36") (pin "-") (pinfunction "-_-") (pintype "passive"))
      (node (ref "C43") (pin "1") (pinfunction "1_1") (pintype "passive"))
      (node (ref "R53") (pin "1") (pinfunction "1_1") (pintype "passive"))
      (node (ref "R54") (pin "2") (pinfunction "2_2") (pintype "passive"))
    )
    (net (code "16") (name "Net-(C37-Pad-)") (class "Default")
      (node (ref "C37") (pin "-") (pinfunction "-_-") (pintype "passive"))
      (node (ref "C44") (pin "1") (pinfunction "1_1") (pintype "passive"))
      (node (ref "R55") (pin "1") (pinfunction "1_1") (pintype "passive"))
      (node (ref "R56") (pin "2") (pinfunction "2_2") (pintype "passive"))
    )
    (net (code "17") (name "Net-(C41-Pad-)") (class "Default")
      (node (ref "C41") (pin "-") (pinfunction "-_-") (pintype "passive"))
      (node (ref "R50") (pin "2") (pinfunction "2_2") (pintype "passive"))
      (node (ref "R52") (pin "2") (pinfunction "2_2") (pintype "passive"))
    )
    (net (code "18") (name "Net-(J1-PadA)") (class "Default")
      (node (ref "J1") (pin "A") (pinfunction "A_A") (pintype "passive"))
      (node (ref "R42") (pin "2") (pinfunction "2_2") (pintype "passive"))
    )
    (net (code "19") (name "Net-(J1-PadC)") (class "Default")
      (node (ref "J1") (pin "C") (pinfunction "C_C") (pintype "passive"))
      (node (ref "J3") (pin "A") (pinfunction "A_A") (pintype "passive"))
    )
    (net (code "20") (name "Net-(J1-PadIN)") (class "Default")
      (node (ref "J1") (pin "IN") (pinfunction "IN_IN") (pintype "passive"))
      (node (ref "R12") (pin "1") (pinfunction "1_1") (pintype "passive"))
    )
    (net (code "21") (name "Net-(J2-PadA)") (class "Default")
      (node (ref "J2") (pin "A") (pinfunction "A_A") (pintype "passive"))
      (node (ref "R60") (pin "2") (pinfunction "2_2") (pintype "passive"))
    )
    (net (code "22") (name "Net-(J2-PadC)") (class "Default")
      (node (ref "J2") (pin "C") (pinfunction "C_C") (pintype "passive"))
      (node (ref "J9") (pin "A") (pinfunction "A_A") (pintype "passive"))
    )
    (net (code "23") (name "Net-(J2-PadIN)") (class "Default")
      (node (ref "J2") (pin "IN") (pinfunction "IN_IN") (pintype "passive"))
      (node (ref "R15") (pin "1") (pinfunction "1_1") (pintype "passive"))
    )
    (net (code "24") (name "Net-(J3-PadC)") (class "Default")
      (node (ref "J3") (pin "C") (pinfunction "C_C") (pintype "passive"))
      (node (ref "J4") (pin "A") (pinfunction "A_A") (pintype "passive"))
    )
    (net (code "25") (name "Net-(J3-PadIN)") (class "Default")
      (node (ref "J3") (pin "IN") (pinfunction "IN_IN") (pintype "passive"))
      (node (ref "R29") (pin "2") (pinfunction "2_2") (pintype "passive"))
    )
    (net (code "26") (name "Net-(J4-PadC)") (class "Default")
      (node (ref "J4") (pin "C") (pinfunction "C_C") (pintype "passive"))
      (node (ref "J5") (pin "A") (pinfunction "A_A") (pintype "passive"))
    )
    (net (code "27") (name "Net-(J4-PadIN)") (class "Default")
      (node (ref "J4") (pin "IN") (pinfunction "IN_IN") (pintype "passive"))
      (node (ref "R21") (pin "2") (pinfunction "2_2") (pintype "passive"))
    )
    (net (code "28") (name "Net-(J5-PadIN)") (class "Default")
      (node (ref "J5") (pin "IN") (pinfunction "IN_IN") (pintype "passive"))
      (node (ref "R38") (pin "2") (pinfunction "2_2") (pintype "passive"))
    )
    (net (code "29") (name "Net-(J6-PadIN)") (class "Default")
      (node (ref "J6") (pin "IN") (pinfunction "IN_IN") (pintype "passive"))
      (node (ref "R39") (pin "2") (pinfunction "2_2") (pintype "passive"))
    )
    (net (code "30") (name "Net-(J7-PadA)") (class "Default")
      (node (ref "J7") (pin "A") (pinfunction "A_A") (pintype "passive"))
      (node (ref "R63") (pin "2") (pinfunction "2_2") (pintype "passive"))
    )
    (net (code "31") (name "Net-(J7-PadC)") (class "Default")
      (node (ref "J7") (pin "C") (pinfunction "C_C") (pintype "passive"))
      (node (ref "J8") (pin "A") (pinfunction "A_A") (pintype "passive"))
    )
    (net (code "32") (name "Net-(J7-PadIN)") (class "Default")
      (node (ref "J7") (pin "IN") (pinfunction "IN_IN") (pintype "passive"))
      (node (ref "J8") (pin "NORM") (pinfunction "NORM_NORM") (pintype "passive"))
      (node (ref "R57") (pin "2") (pinfunction "2_2") (pintype "passive"))
    )
    (net (code "33") (name "Net-(J8-PadIN)") (class "Default")
      (node (ref "J8") (pin "IN") (pinfunction "IN_IN") (pintype "passive"))
      (node (ref "R58") (pin "2") (pinfunction "2_2") (pintype "passive"))
    )
    (net (code "34") (name "Net-(J9-PadIN)") (class "Default")
      (node (ref "J9") (pin "IN") (pinfunction "IN_IN") (pintype "passive"))
      (node (ref "R32") (pin "2") (pinfunction "2_2") (pintype "passive"))
    )
    (net (code "35") (name "Net-(J10-PadA)") (class "Default")
      (node (ref "J10") (pin "A") (pinfunction "A_A") (pintype "passive"))
      (node (ref "J9") (pin "C") (pinfunction "C_C") (pintype "passive"))
    )
    (net (code "36") (name "Net-(J10-PadC)") (class "Default")
      (node (ref "J10") (pin "C") (pinfunction "C_C") (pintype "passive"))
      (node (ref "J6") (pin "A") (pinfunction "A_A") (pintype "passive"))
    )
    (net (code "37") (name "Net-(J10-PadIN)") (class "Default")
      (node (ref "J10") (pin "IN") (pinfunction "IN_IN") (pintype "passive"))
      (node (ref "R24") (pin "2") (pinfunction "2_2") (pintype "passive"))
    )
    (net (code "38") (name "Net-(J11-PadA)") (class "Default")
      (node (ref "J11") (pin "A") (pinfunction "A_A") (pintype "passive"))
      (node (ref "J8") (pin "C") (pinfunction "C_C") (pintype "passive"))
    )
    (net (code "39") (name "Net-(J11-PadC)") (class "Default")
      (node (ref "J11") (pin "C") (pinfunction "C_C") (pintype "passive"))
      (node (ref "J12") (pin "A") (pinfunction "A_A") (pintype "passive"))
    )
    (net (code "40") (name "Net-(J11-PadIN)") (class "Default")
      (node (ref "J11") (pin "IN") (pinfunction "IN_IN") (pintype "passive"))
      (node (ref "R61") (pin "1") (pinfunction "1_1") (pintype "passive"))
    )
    (net (code "41") (name "Net-(J12-PadIN)") (class "Default")
      (node (ref "J12") (pin "IN") (pinfunction "IN_IN") (pintype "passive"))
      (node (ref "R62") (pin "1") (pinfunction "1_1") (pintype "passive"))
    )
    (net (code "42") (name "Net-(JP68-Pad1)") (class "Default")
      (node (ref "JP68") (pin "1") (pinfunction "1_1") (pintype "passive"))
      (node (ref "R42") (pin "1") (pinfunction "1_1") (pintype "passive"))
      (node (ref "R60") (pin "1") (pinfunction "1_1") (pintype "passive"))
      (node (ref "R63") (pin "1") (pinfunction "1_1") (pintype "passive"))
    )
    (net (code "43") (name "Net-(L1-PadA)") (class "Default")
      (node (ref "L1") (pin "A") (pinfunction "A_A") (pintype "passive"))
      (node (ref "R1") (pin "2") (pinfunction "2_2") (pintype "passive"))
      (node (ref "R2") (pin "2") (pinfunction "2_2") (pintype "passive"))
    )
    (net (code "44") (name "Net-(LED1-GRN)") (class "Default")
      (node (ref "LED1") (pin "1") (pinfunction "GRN_1") (pintype "bidirectional"))
      (node (ref "R4") (pin "1") (pinfunction "1_1") (pintype "passive"))
    )
    (net (code "45") (name "Net-(LED1-RED)") (class "Default")
      (node (ref "LED1") (pin "3") (pinfunction "RED_3") (pintype "bidirectional"))
      (node (ref "R3") (pin "1") (pinfunction "1_1") (pintype "passive"))
    )
    (net (code "46") (name "Net-(LED2-GRN)") (class "Default")
      (node (ref "LED2") (pin "1") (pinfunction "GRN_1") (pintype "bidirectional"))
      (node (ref "R5") (pin "1") (pinfunction "1_1") (pintype "passive"))
    )
    (net (code "47") (name "Net-(LED2-RED)") (class "Default")
      (node (ref "LED2") (pin "3") (pinfunction "RED_3") (pintype "bidirectional"))
      (node (ref "R6") (pin "1") (pinfunction "1_1") (pintype "passive"))
    )
    (net (code "48") (name "Net-(LED3-GRN)") (class "Default")
      (node (ref "LED3") (pin "1") (pinfunction "GRN_1") (pintype "bidirectional"))
      (node (ref "R7") (pin "1") (pinfunction "1_1") (pintype "passive"))
    )
    (net (code "49") (name "Net-(LED3-RED)") (class "Default")
      (node (ref "LED3") (pin "3") (pinfunction "RED_3") (pintype "bidirectional"))
      (node (ref "R8") (pin "1") (pinfunction "1_1") (pintype "passive"))
    )
    (net (code "50") (name "Net-(LED4-GRN)") (class "Default")
      (node (ref "LED4") (pin "1") (pinfunction "GRN_1") (pintype "bidirectional"))
      (node (ref "R9") (pin "1") (pinfunction "1_1") (pintype "passive"))
    )
    (net (code "51") (name "Net-(LED4-RED)") (class "Default")
      (node (ref "LED4") (pin "3") (pinfunction "RED_3") (pintype "bidirectional"))
      (node (ref "R10") (pin "1") (pinfunction "1_1") (pintype "passive"))
    )
    (net (code "52") (name "Net-(POT1A-A)") (class "Default")
      (node (ref "POT1") (pin "R1_1") (pinfunction "A_R1_1") (pintype "passive"))
      (node (ref "R46") (pin "1") (pinfunction "1_1") (pintype "passive"))
    )
    (net (code "53") (name "Net-(POT1A-B)") (class "Default")
      (node (ref "POT1") (pin "R1_2") (pinfunction "W_R1_2") (pintype "passive"))
      (node (ref "POT1") (pin "R1_3") (pinfunction "B_R1_3") (pintype "passive"))
      (node (ref "R55") (pin "2") (pinfunction "2_2") (pintype "passive"))
      (node (ref "U5") (pin "1") (pinfunction "P$3_1") (pintype "bidirectional"))
    )
    (net (code "54") (name "Net-(POT1B-A)") (class "Default")
      (node (ref "POT1") (pin "R2_1") (pinfunction "A_R2_1") (pintype "passive"))
      (node (ref "R47") (pin "1") (pinfunction "1_1") (pintype "passive"))
    )
    (net (code "55") (name "Net-(POT1B-B)") (class "Default")
      (node (ref "POT1") (pin "R2_2") (pinfunction "W_R2_2") (pintype "passive"))
      (node (ref "POT1") (pin "R2_3") (pinfunction "B_R2_3") (pintype "passive"))
      (node (ref "R53") (pin "2") (pinfunction "2_2") (pintype "passive"))
      (node (ref "U5") (pin "7") (pinfunction "P$3_7") (pintype "bidirectional"))
    )
    (net (code "56") (name "Net-(Q1-B)") (class "Default")
      (node (ref "Q1") (pin "1") (pinfunction "B_1") (pintype "passive"))
      (node (ref "R12") (pin "2") (pinfunction "2_2") (pintype "passive"))
    )
    (net (code "57") (name "Net-(Q2-B)") (class "Default")
      (node (ref "Q2") (pin "1") (pinfunction "B_1") (pintype "passive"))
      (node (ref "R15") (pin "2") (pinfunction "2_2") (pintype "passive"))
    )
    (net (code "58") (name "Net-(R18-W)") (class "Default")
      (node (ref "R18") (pin "2") (pinfunction "W_2") (pintype "passive"))
      (node (ref "R28") (pin "2") (pinfunction "2_2") (pintype "passive"))
    )
    (net (code "59") (name "Net-(R43-W)") (class "Default")
      (node (ref "R33") (pin "2") (pinfunction "2_2") (pintype "passive"))
      (node (ref "R43") (pin "2") (pinfunction "W_2") (pintype "passive"))
    )
    (net (code "60") (name "Net-(U1A-P$2)") (class "Default")
      (node (ref "C9") (pin "1") (pinfunction "1_1") (pintype "passive"))
      (node (ref "R27") (pin "2") (pinfunction "2_2") (pintype "passive"))
      (node (ref "R28") (pin "1") (pinfunction "1_1") (pintype "passive"))
      (node (ref "R29") (pin "1") (pinfunction "1_1") (pintype "passive"))
      (node (ref "U1") (pin "2") (pinfunction "P$2_2") (pintype "bidirectional"))
    )
    (net (code "61") (name "Net-(U1B-P$2)") (class "Default")
      (node (ref "C22") (pin "1") (pinfunction "1_1") (pintype "passive"))
      (node (ref "R31") (pin "2") (pinfunction "2_2") (pintype "passive"))
      (node (ref "R32") (pin "1") (pinfunction "1_1") (pintype "passive"))
      (node (ref "R33") (pin "1") (pinfunction "1_1") (pintype "passive"))
      (node (ref "U1") (pin "6") (pinfunction "P$2_6") (pintype "bidirectional"))
    )
    (net (code "62") (name "Net-(U2A-P$2)") (class "Default")
      (node (ref "C20") (pin "1") (pinfunction "1_1") (pintype "passive"))
      (node (ref "R34") (pin "2") (pinfunction "2_2") (pintype "passive"))
      (node (ref "R36") (pin "1") (pinfunction "1_1") (pintype "passive"))
      (node (ref "R38") (pin "1") (pinfunction "1_1") (pintype "passive"))
      (node (ref "U2") (pin "2") (pinfunction "P$2_2") (pintype "bidirectional"))
    )
    (net (code "63") (name "Net-(U2B-P$2)") (class "Default")
      (node (ref "C10") (pin "1") (pinfunction "1_1") (pintype "passive"))
      (node (ref "R21") (pin "1") (pinfunction "1_1") (pintype "passive"))
      (node (ref "R22") (pin "1") (pinfunction "1_1") (pintype "passive"))
      (node (ref "R25") (pin "2") (pinfunction "2_2") (pintype "passive"))
      (node (ref "U2") (pin "6") (pinfunction "P$2_6") (pintype "bidirectional"))
    )
    (net (code "64") (name "Net-(U3A-P$2)") (class "Default")
      (node (ref "C21") (pin "1") (pinfunction "1_1") (pintype "passive"))
      (node (ref "R35") (pin "2") (pinfunction "2_2") (pintype "passive"))
      (node (ref "R37") (pin "1") (pinfunction "1_1") (pintype "passive"))
      (node (ref "R39") (pin "1") (pinfunction "1_1") (pintype "passive"))
      (node (ref "U3") (pin "2") (pinfunction "P$2_2") (pintype "bidirectional"))
    )
    (net (code "65") (name "Net-(U3B-P$2)") (class "Default")
      (node (ref "C11") (pin "1") (pinfunction "1_1") (pintype "passive"))
      (node (ref "R23") (pin "1") (pinfunction "1_1") (pintype "passive"))
      (node (ref "R24") (pin "1") (pinfunction "1_1") (pintype "passive"))
      (node (ref "R26") (pin "2") (pinfunction "2_2") (pintype "passive"))
      (node (ref "U3") (pin "6") (pinfunction "P$2_6") (pintype "bidirectional"))
    )
    (net (code "66") (name "Net-(U4-QA)") (class "Default")
      (node (ref "R10") (pin "2") (pinfunction "2_2") (pintype "passive"))
      (node (ref "U4") (pin "15") (pinfunction "QA_15") (pintype "output"))
    )
    (net (code "67") (name "Net-(U4-QB)") (class "Default")
      (node (ref "R9") (pin "2") (pinfunction "2_2") (pintype "passive"))
      (node (ref "U4") (pin "1") (pinfunction "QB_1") (pintype "output"))
    )
    (net (code "68") (name "Net-(U4-QC)") (class "Default")
      (node (ref "R8") (pin "2") (pinfunction "2_2") (pintype "passive"))
      (node (ref "U4") (pin "2") (pinfunction "QC_2") (pintype "output"))
    )
    (net (code "69") (name "Net-(U4-QD)") (class "Default")
      (node (ref "R7") (pin "2") (pinfunction "2_2") (pintype "passive"))
      (node (ref "U4") (pin "3") (pinfunction "QD_3") (pintype "output"))
    )
    (net (code "70") (name "Net-(U4-QE)") (class "Default")
      (node (ref "R6") (pin "2") (pinfunction "2_2") (pintype "passive"))
      (node (ref "U4") (pin "4") (pinfunction "QE_4") (pintype "output"))
    )
    (net (code "71") (name "Net-(U4-QF)") (class "Default")
      (node (ref "R5") (pin "2") (pinfunction "2_2") (pintype "passive"))
      (node (ref "U4") (pin "5") (pinfunction "QF_5") (pintype "output"))
    )
    (net (code "72") (name "Net-(U4-QG)") (class "Default")
      (node (ref "R3") (pin "2") (pinfunction "2_2") (pintype "passive"))
      (node (ref "U4") (pin "6") (pinfunction "QG_6") (pintype "output"))
    )
    (net (code "73") (name "Net-(U4-QH)") (class "Default")
      (node (ref "R4") (pin "2") (pinfunction "2_2") (pintype "passive"))
      (node (ref "U4") (pin "7") (pinfunction "QH_7") (pintype "output"))
    )
    (net (code "74") (name "Net-(U5A-P$2)") (class "Default")
      (node (ref "R46") (pin "2") (pinfunction "2_2") (pintype "passive"))
      (node (ref "R57") (pin "1") (pinfunction "1_1") (pintype "passive"))
      (node (ref "U5") (pin "2") (pinfunction "P$2_2") (pintype "bidirectional"))
    )
    (net (code "75") (name "Net-(U5B-P$2)") (class "Default")
      (node (ref "R47") (pin "2") (pinfunction "2_2") (pintype "passive"))
      (node (ref "R58") (pin "1") (pinfunction "1_1") (pintype "passive"))
      (node (ref "U5") (pin "6") (pinfunction "P$2_6") (pintype "bidirectional"))
    )
    (net (code "76") (name "Net-(U6A-P$2)") (class "Default")
      (node (ref "C40") (pin "1") (pinfunction "1_1") (pintype "passive"))
      (node (ref "R49") (pin "2") (pinfunction "2_2") (pintype "passive"))
      (node (ref "R51") (pin "1") (pinfunction "1_1") (pintype "passive"))
      (node (ref "U6") (pin "2") (pinfunction "P$2_2") (pintype "bidirectional"))
    )
    (net (code "77") (name "Net-(U6A-P$3)") (class "Default")
      (node (ref "C40") (pin "2") (pinfunction "2_2") (pintype "passive"))
      (node (ref "R49") (pin "1") (pinfunction "1_1") (pintype "passive"))
      (node (ref "R61") (pin "2") (pinfunction "2_2") (pintype "passive"))
      (node (ref "U6") (pin "1") (pinfunction "P$3_1") (pintype "bidirectional"))
    )
    (net (code "78") (name "Net-(U6B-P$2)") (class "Default")
      (node (ref "C42") (pin "1") (pinfunction "1_1") (pintype "passive"))
      (node (ref "R48") (pin "2") (pinfunction "2_2") (pintype "passive"))
      (node (ref "R52") (pin "1") (pinfunction "1_1") (pintype "passive"))
      (node (ref "U6") (pin "6") (pinfunction "P$2_6") (pintype "bidirectional"))
    )
    (net (code "79") (name "Net-(U6B-P$3)") (class "Default")
      (node (ref "C42") (pin "2") (pinfunction "2_2") (pintype "passive"))
      (node (ref "R48") (pin "1") (pinfunction "1_1") (pintype "passive"))
      (node (ref "R62") (pin "2") (pinfunction "2_2") (pintype "passive"))
      (node (ref "U6") (pin "7") (pinfunction "P$3_7") (pintype "bidirectional"))
    )
    (net (code "80") (name "PITCH_POT") (class "Default")
      (node (ref "JP15") (pin "1") (pinfunction "1_1") (pintype "passive"))
      (node (ref "R20") (pin "2") (pinfunction "W_2") (pintype "passive"))
    )
    (net (code "81") (name "PLAY") (class "Default")
      (node (ref "JP23") (pin "1") (pinfunction "1_1") (pintype "passive"))
      (node (ref "Q2") (pin "3") (pinfunction "C_3") (pintype "passive"))
      (node (ref "R16") (pin "1") (pinfunction "1_1") (pintype "passive"))
    )
    (net (code "82") (name "POSITION_POT_CV") (class "Default")
      (node (ref "C9") (pin "2") (pinfunction "2_2") (pintype "passive"))
      (node (ref "JP5") (pin "1") (pinfunction "1_1") (pintype "passive"))
      (node (ref "R27") (pin "1") (pinfunction "1_1") (pintype "passive"))
      (node (ref "U1") (pin "1") (pinfunction "P$3_1") (pintype "bidirectional"))
    )
    (net (code "83") (name "REC") (class "Default")
      (node (ref "JP22") (pin "1") (pinfunction "1_1") (pintype "passive"))
      (node (ref "Q1") (pin "3") (pinfunction "C_3") (pintype "passive"))
      (node (ref "R14") (pin "1") (pinfunction "1_1") (pintype "passive"))
    )
    (net (code "84") (name "RIN") (class "Default")
      (node (ref "C36") (pin "+") (pinfunction "+_+") (pintype "passive"))
      (node (ref "JP27") (pin "1") (pinfunction "1_1") (pintype "passive"))
    )
    (net (code "85") (name "ROUT") (class "Default")
      (node (ref "C41") (pin "+") (pinfunction "+_+") (pintype "passive"))
      (node (ref "JP30") (pin "1") (pinfunction "1_1") (pintype "passive"))
    )
    (net (code "86") (name "SIZE_CV") (class "Default")
      (node (ref "C10") (pin "2") (pinfunction "2_2") (pintype "passive"))
      (node (ref "JP9") (pin "1") (pinfunction "1_1") (pintype "passive"))
      (node (ref "R25") (pin "1") (pinfunction "1_1") (pintype "passive"))
      (node (ref "U2") (pin "7") (pinfunction "P$3_7") (pintype "bidirectional"))
    )
    (net (code "87") (name "SIZE_POT") (class "Default")
      (node (ref "JP13") (pin "1") (pinfunction "1_1") (pintype "passive"))
      (node (ref "R19") (pin "2") (pinfunction "W_2") (pintype "passive"))
    )
    (net (code "88") (name "SW_LOAD") (class "Default")
      (node (ref "JP18") (pin "1") (pinfunction "1_1") (pintype "passive"))
      (node (ref "SW3") (pin "3") (pinfunction "3_3") (pintype "passive"))
      (node (ref "SW3") (pin "4") (pinfunction "4_4") (pintype "passive"))
    )
    (net (code "89") (name "SW_MODE") (class "Default")
      (node (ref "JP17") (pin "1") (pinfunction "1_1") (pintype "passive"))
      (node (ref "SW2") (pin "3") (pinfunction "3_3") (pintype "passive"))
      (node (ref "SW2") (pin "4") (pinfunction "4_4") (pintype "passive"))
    )
    (net (code "90") (name "SW_REC") (class "Default")
      (node (ref "JP24") (pin "1") (pinfunction "1_1") (pintype "passive"))
      (node (ref "SW1") (pin "1") (pinfunction "1_1") (pintype "passive"))
      (node (ref "SW1") (pin "2") (pinfunction "2_2") (pintype "passive"))
    )
    (net (code "91") (name "TEXTURE_CV") (class "Default")
      (node (ref "C11") (pin "2") (pinfunction "2_2") (pintype "passive"))
      (node (ref "JP8") (pin "1") (pinfunction "1_1") (pintype "passive"))
      (node (ref "R26") (pin "1") (pinfunction "1_1") (pintype "passive"))
      (node (ref "U3") (pin "7") (pinfunction "P$3_7") (pintype "bidirectional"))
    )
    (net (code "92") (name "TEXTURE_POT") (class "Default")
      (node (ref "JP14") (pin "1") (pinfunction "1_1") (pintype "passive"))
      (node (ref "R44") (pin "2") (pinfunction "W_2") (pintype "passive"))
    )
    (net (code "93") (name "VCC") (class "Default")
      (node (ref "C38") (pin "1") (pinfunction "1_1") (pintype "passive"))
      (node (ref "C39") (pin "1") (pinfunction "1_1") (pintype "passive"))
      (node (ref "JP31") (pin "1") (pinfunction "1_1") (pintype "passive"))
      (node (ref "U5") (pin "8") (pinfunction "P$1_8") (pintype "bidirectional"))
      (node (ref "U6") (pin "8") (pinfunction "P$1_8") (pintype "bidirectional"))
    )
    (net (code "94") (name "VEE") (class "Default")
      (node (ref "C45") (pin "2") (pinfunction "2_2") (pintype "passive"))
      (node (ref "C46") (pin "2") (pinfunction "2_2") (pintype "passive"))
      (node (ref "JP32") (pin "1") (pinfunction "1_1") (pintype "passive"))
      (node (ref "U5") (pin "4") (pinfunction "P$2_4") (pintype "bidirectional"))
      (node (ref "U6") (pin "4") (pinfunction "P$2_4") (pintype "bidirectional"))
    )
    (net (code "95") (name "V_OCT") (class "Default")
      (node (ref "C20") (pin "2") (pinfunction "2_2") (pintype "passive"))
      (node (ref "JP6") (pin "1") (pinfunction "1_1") (pintype "passive"))
      (node (ref "R34") (pin "1") (pinfunction "1_1") (pintype "passive"))
      (node (ref "U2") (pin "1") (pinfunction "P$3_1") (pintype "bidirectional"))
    )
    (net (code "96") (name "unconnected-(J3-PadNORM)") (class "Default")
      (node (ref "J3") (pin "NORM") (pinfunction "NORM_NORM") (pintype "passive"))
    )
    (net (code "97") (name "unconnected-(J4-PadNORM)") (class "Default")
      (node (ref "J4") (pin "NORM") (pinfunction "NORM_NORM") (pintype "passive"))
    )
    (net (code "98") (name "unconnected-(J5-PadNORM)") (class "Default")
      (node (ref "J5") (pin "NORM") (pinfunction "NORM_NORM") (pintype "passive"))
    )
    (net (code "99") (name "unconnected-(J6-PadNORM)") (class "Default")
      (node (ref "J6") (pin "NORM") (pinfunction "NORM_NORM") (pintype "passive"))
    )
    (net (code "100") (name "unconnected-(J7-PadNORM)") (class "Default")
      (node (ref "J7") (pin "NORM") (pinfunction "NORM_NORM") (pintype "passive"))
    )
    (net (code "101") (name "unconnected-(J9-PadNORM)") (class "Default")
      (node (ref "J9") (pin "NORM") (pinfunction "NORM_NORM") (pintype "passive"))
    )
    (net (code "102") (name "unconnected-(J10-PadNORM)") (class "Default")
      (node (ref "J10") (pin "NORM") (pinfunction "NORM_NORM") (pintype "passive"))
    )
    (net (code "103") (name "unconnected-(J11-PadNORM)") (class "Default")
      (node (ref "J11") (pin "NORM") (pinfunction "NORM_NORM") (pintype "passive"))
    )
    (net (code "104") (name "unconnected-(J12-PadNORM)") (class "Default")
      (node (ref "J12") (pin "NORM") (pinfunction "NORM_NORM") (pintype "passive"))
    )
    (net (code "105") (name "unconnected-(U4-QH_2-Pad9)") (class "Default")
      (node (ref "U4") (pin "9") (pinfunction "QH_2_9") (pintype "output"))
    )
  )
)
